# reverse_protection.net
KiCad netlist of a schematic drawn in Altium Designer
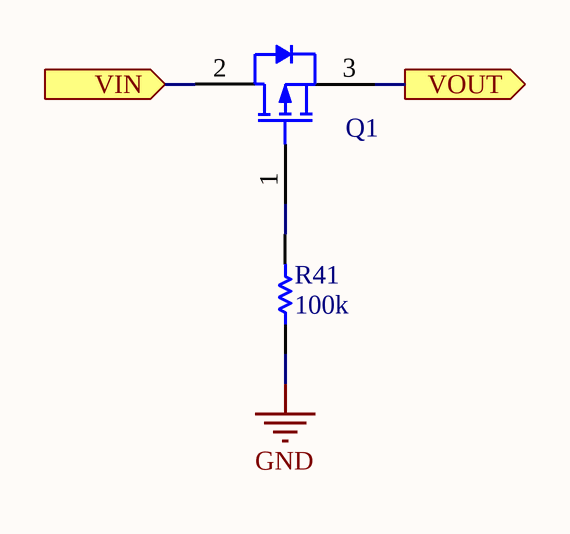
[diagram p0: reverse_protection.SchDoc]

(export (version "E")
  (design (tool "Eeschema 10.0.6"))
  (components
    (comp (ref "Q1")
      (value "Infineon IPD90P04P405ATMA1")
      (footprint "PCB-n8uhnm53xyssvg7v0f21-1")
      (description "Single P-Channel 40 V 4.7 mOhm 118 nC OptiMOS Power Mosfet - TO-252-3")
      (fields (field (name "MANUFACTURER PART NUMBER") "IPD90P04P405ATMA1"))
      (libsource (lib "CommunityVault") (part "CMP-b5fa7db8f8eb6a3d-1"))
    )
    (comp (ref "R41")
      (value "100k")
      (footprint "RESC1609X50X30LL10T20")
      (description "RES SMD 100K OHM 1% 1/10W 0603")
      (libsource (lib "CommunityVault") (part "CMP-16231689-4"))
    )
  )
  (nets
    (net (code "1") (name "/VIN") (class "Default")
      (node (ref "Q1") (pin "2") (pinfunction "D_2") (pintype "passive"))
    )
    (net (code "2") (name "/VOUT") (class "Default")
      (node (ref "Q1") (pin "3") (pinfunction "S_3") (pintype "passive"))
    )
    (net (code "3") (name "GND") (class "Default")
      (node (ref "R41") (pin "1") (pinfunction "1_1") (pintype "passive"))
    )
    (net (code "4") (name "Net-(Q1-G)") (class "Default")
      (node (ref "Q1") (pin "1") (pinfunction "G_1") (pintype "passive"))
      (node (ref "R41") (pin "2") (pinfunction "2_2") (pintype "passive"))
    )
  )
)
